# master_camera_io_2.net
KiCad netlist of a schematic drawn in EAGLE
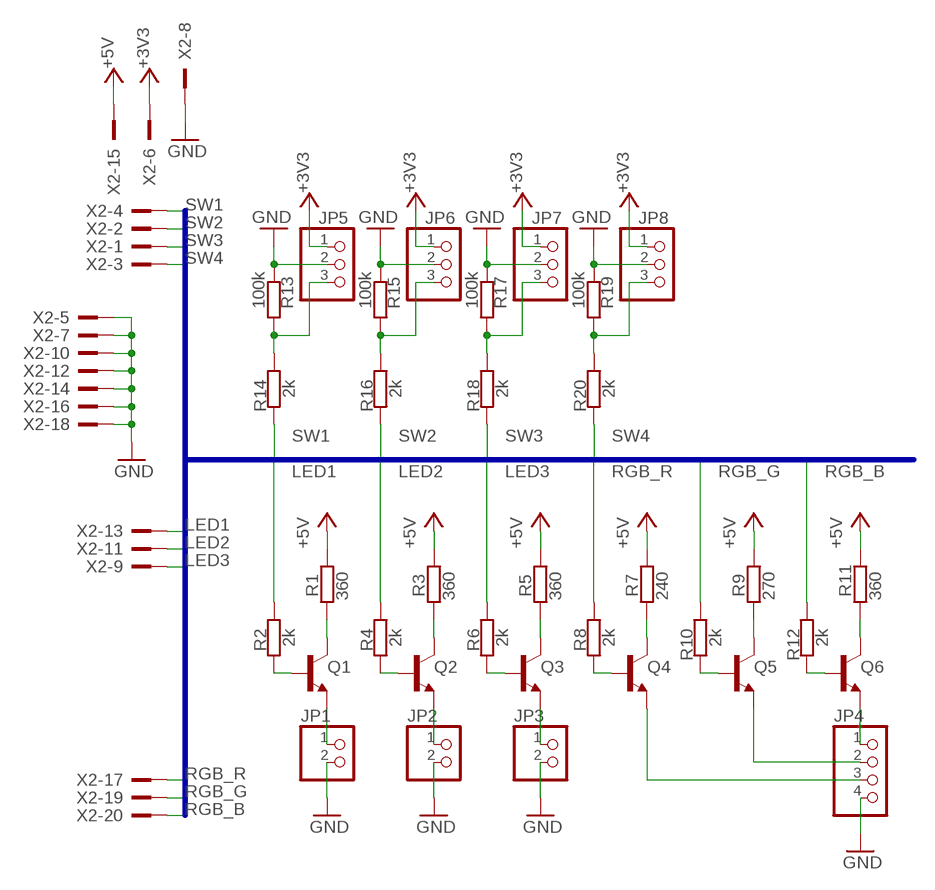
[diagram p0: schematic, sheet 1]

(export (version "E")
  (design (tool "Eeschema 10.0.6"))
  (components
    (comp (ref "JP1")
      (value "PINHD-1X2")
      (footprint "eagle-import:1X02")
      (libsource (lib "eagle-import") (part "PINHD-1X2"))
    )
    (comp (ref "JP2")
      (value "PINHD-1X2")
      (footprint "eagle-import:1X02")
      (libsource (lib "eagle-import") (part "PINHD-1X2"))
    )
    (comp (ref "JP3")
      (value "PINHD-1X2")
      (footprint "eagle-import:1X02")
      (libsource (lib "eagle-import") (part "PINHD-1X2"))
    )
    (comp (ref "JP4")
      (value "PINHD-1X4")
      (footprint "eagle-import:1X04")
      (libsource (lib "eagle-import") (part "PINHD-1X4"))
    )
    (comp (ref "JP5")
      (value "PINHD-1X3")
      (footprint "eagle-import:1X03")
      (libsource (lib "eagle-import") (part "PINHD-1X3"))
    )
    (comp (ref "JP6")
      (value "PINHD-1X3")
      (footprint "eagle-import:1X03")
      (libsource (lib "eagle-import") (part "PINHD-1X3"))
    )
    (comp (ref "JP7")
      (value "PINHD-1X3")
      (footprint "eagle-import:1X03")
      (libsource (lib "eagle-import") (part "PINHD-1X3"))
    )
    (comp (ref "JP8")
      (value "PINHD-1X3")
      (footprint "eagle-import:1X03")
      (libsource (lib "eagle-import") (part "PINHD-1X3"))
    )
    (comp (ref "Q1")
      (value "BC850SMD")
      (footprint "eagle-import:SOT23-BEC")
      (libsource (lib "eagle-import") (part "BC850SMD"))
    )
    (comp (ref "Q2")
      (value "BC850SMD")
      (footprint "eagle-import:SOT23-BEC")
      (libsource (lib "eagle-import") (part "BC850SMD"))
    )
    (comp (ref "Q3")
      (value "BC850SMD")
      (footprint "eagle-import:SOT23-BEC")
      (libsource (lib "eagle-import") (part "BC850SMD"))
    )
    (comp (ref "Q4")
      (value "BC850SMD")
      (footprint "eagle-import:SOT23-BEC")
      (libsource (lib "eagle-import") (part "BC850SMD"))
    )
    (comp (ref "Q5")
      (value "BC850SMD")
      (footprint "eagle-import:SOT23-BEC")
      (libsource (lib "eagle-import") (part "BC850SMD"))
    )
    (comp (ref "Q6")
      (value "BC850SMD")
      (footprint "eagle-import:SOT23-BEC")
      (libsource (lib "eagle-import") (part "BC850SMD"))
    )
    (comp (ref "R1")
      (value "360")
      (footprint "eagle-import:R0805")
      (libsource (lib "eagle-import") (part "R-EU_R0805"))
    )
    (comp (ref "R2")
      (value "2k")
      (footprint "eagle-import:R0805")
      (libsource (lib "eagle-import") (part "R-EU_R0805"))
    )
    (comp (ref "R3")
      (value "360")
      (footprint "eagle-import:R0805")
      (libsource (lib "eagle-import") (part "R-EU_R0805"))
    )
    (comp (ref "R4")
      (value "2k")
      (footprint "eagle-import:R0805")
      (libsource (lib "eagle-import") (part "R-EU_R0805"))
    )
    (comp (ref "R5")
      (value "360")
      (footprint "eagle-import:R0805")
      (libsource (lib "eagle-import") (part "R-EU_R0805"))
    )
    (comp (ref "R6")
      (value "2k")
      (footprint "eagle-import:R0805")
      (libsource (lib "eagle-import") (part "R-EU_R0805"))
    )
    (comp (ref "R7")
      (value "240")
      (footprint "eagle-import:R0805")
      (libsource (lib "eagle-import") (part "R-EU_R0805"))
    )
    (comp (ref "R8")
      (value "2k")
      (footprint "eagle-import:R0805")
      (libsource (lib "eagle-import") (part "R-EU_R0805"))
    )
    (comp (ref "R9")
      (value "270")
      (footprint "eagle-import:R0805")
      (libsource (lib "eagle-import") (part "R-EU_R0805"))
    )
    (comp (ref "R10")
      (value "2k")
      (footprint "eagle-import:R0805")
      (libsource (lib "eagle-import") (part "R-EU_R0805"))
    )
    (comp (ref "R11")
      (value "360")
      (footprint "eagle-import:R0805")
      (libsource (lib "eagle-import") (part "R-EU_R0805"))
    )
    (comp (ref "R12")
      (value "2k")
      (footprint "eagle-import:R0805")
      (libsource (lib "eagle-import") (part "R-EU_R0805"))
    )
    (comp (ref "R13")
      (value "100k")
      (footprint "eagle-import:R0805")
      (libsource (lib "eagle-import") (part "R-EU_R0805"))
    )
    (comp (ref "R14")
      (value "2k")
      (footprint "eagle-import:R0805")
      (libsource (lib "eagle-import") (part "R-EU_R0805"))
    )
    (comp (ref "R15")
      (value "100k")
      (footprint "eagle-import:R0805")
      (libsource (lib "eagle-import") (part "R-EU_R0805"))
    )
    (comp (ref "R16")
      (value "2k")
      (footprint "eagle-import:R0805")
      (libsource (lib "eagle-import") (part "R-EU_R0805"))
    )
    (comp (ref "R17")
      (value "100k")
      (footprint "eagle-import:R0805")
      (libsource (lib "eagle-import") (part "R-EU_R0805"))
    )
    (comp (ref "R18")
      (value "2k")
      (footprint "eagle-import:R0805")
      (libsource (lib "eagle-import") (part "R-EU_R0805"))
    )
    (comp (ref "R19")
      (value "100k")
      (footprint "eagle-import:R0805")
      (libsource (lib "eagle-import") (part "R-EU_R0805"))
    )
    (comp (ref "R20")
      (value "2k")
      (footprint "eagle-import:R0805")
      (libsource (lib "eagle-import") (part "R-EU_R0805"))
    )
    (comp (ref "X2")
      (value "2520-")
      (footprint "eagle-import:PAK100_2500-20")
      (libsource (lib "eagle-import") (part "2520-"))
    )
  )
  (nets
    (net (code "1") (name "+3V3") (class "Default")
      (node (ref "JP5") (pin "1") (pinfunction "1_1") (pintype "passive"))
      (node (ref "JP6") (pin "1") (pinfunction "1_1") (pintype "passive"))
      (node (ref "JP7") (pin "1") (pinfunction "1_1") (pintype "passive"))
      (node (ref "JP8") (pin "1") (pinfunction "1_1") (pintype "passive"))
      (node (ref "X2") (pin "6") (pinfunction "KL_6") (pintype "passive"))
    )
    (net (code "2") (name "+5V") (class "Default")
      (node (ref "R1") (pin "2") (pinfunction "2_2") (pintype "passive"))
      (node (ref "R11") (pin "2") (pinfunction "2_2") (pintype "passive"))
      (node (ref "R3") (pin "2") (pinfunction "2_2") (pintype "passive"))
      (node (ref "R5") (pin "2") (pinfunction "2_2") (pintype "passive"))
      (node (ref "R7") (pin "2") (pinfunction "2_2") (pintype "passive"))
      (node (ref "R9") (pin "2") (pinfunction "2_2") (pintype "passive"))
      (node (ref "X2") (pin "15") (pinfunction "KL_15") (pintype "passive"))
    )
    (net (code "3") (name "/LED1") (class "Default")
      (node (ref "R2") (pin "1") (pinfunction "1_1") (pintype "passive"))
      (node (ref "X2") (pin "13") (pinfunction "KL_13") (pintype "passive"))
    )
    (net (code "4") (name "/LED2") (class "Default")
      (node (ref "R4") (pin "1") (pinfunction "1_1") (pintype "passive"))
      (node (ref "X2") (pin "11") (pinfunction "KL_11") (pintype "passive"))
    )
    (net (code "5") (name "/LED3") (class "Default")
      (node (ref "R6") (pin "1") (pinfunction "1_1") (pintype "passive"))
      (node (ref "X2") (pin "9") (pinfunction "KL_9") (pintype "passive"))
    )
    (net (code "6") (name "/RGB_B") (class "Default")
      (node (ref "R12") (pin "1") (pinfunction "1_1") (pintype "passive"))
      (node (ref "X2") (pin "20") (pinfunction "KL_20") (pintype "passive"))
    )
    (net (code "7") (name "/RGB_G") (class "Default")
      (node (ref "R10") (pin "1") (pinfunction "1_1") (pintype "passive"))
      (node (ref "X2") (pin "19") (pinfunction "KL_19") (pintype "passive"))
    )
    (net (code "8") (name "/RGB_R") (class "Default")
      (node (ref "R8") (pin "1") (pinfunction "1_1") (pintype "passive"))
      (node (ref "X2") (pin "17") (pinfunction "KL_17") (pintype "passive"))
    )
    (net (code "9") (name "/SW1") (class "Default")
      (node (ref "R14") (pin "2") (pinfunction "2_2") (pintype "passive"))
      (node (ref "X2") (pin "4") (pinfunction "KL_4") (pintype "passive"))
    )
    (net (code "10") (name "/SW2") (class "Default")
      (node (ref "R16") (pin "2") (pinfunction "2_2") (pintype "passive"))
      (node (ref "X2") (pin "2") (pinfunction "KL_2") (pintype "passive"))
    )
    (net (code "11") (name "/SW3") (class "Default")
      (node (ref "R18") (pin "2") (pinfunction "2_2") (pintype "passive"))
      (node (ref "X2") (pin "1") (pinfunction "KL_1") (pintype "passive"))
    )
    (net (code "12") (name "/SW4") (class "Default")
      (node (ref "R20") (pin "2") (pinfunction "2_2") (pintype "passive"))
      (node (ref "X2") (pin "3") (pinfunction "KL_3") (pintype "passive"))
    )
    (net (code "13") (name "GND") (class "Default")
      (node (ref "JP1") (pin "2") (pinfunction "2_2") (pintype "passive"))
      (node (ref "JP2") (pin "2") (pinfunction "2_2") (pintype "passive"))
      (node (ref "JP3") (pin "2") (pinfunction "2_2") (pintype "passive"))
      (node (ref "JP4") (pin "4") (pinfunction "4_4") (pintype "passive"))
      (node (ref "JP5") (pin "2") (pinfunction "2_2") (pintype "passive"))
      (node (ref "JP6") (pin "2") (pinfunction "2_2") (pintype "passive"))
      (node (ref "JP7") (pin "2") (pinfunction "2_2") (pintype "passive"))
      (node (ref "JP8") (pin "2") (pinfunction "2_2") (pintype "passive"))
      (node (ref "R13") (pin "2") (pinfunction "2_2") (pintype "passive"))
      (node (ref "R15") (pin "2") (pinfunction "2_2") (pintype "passive"))
      (node (ref "R17") (pin "2") (pinfunction "2_2") (pintype "passive"))
      (node (ref "R19") (pin "2") (pinfunction "2_2") (pintype "passive"))
      (node (ref "X2") (pin "10") (pinfunction "KL_10") (pintype "passive"))
      (node (ref "X2") (pin "12") (pinfunction "KL_12") (pintype "passive"))
      (node (ref "X2") (pin "14") (pinfunction "KL_14") (pintype "passive"))
      (node (ref "X2") (pin "16") (pinfunction "KL_16") (pintype "passive"))
      (node (ref "X2") (pin "18") (pinfunction "KL_18") (pintype "passive"))
      (node (ref "X2") (pin "5") (pinfunction "KL_5") (pintype "passive"))
      (node (ref "X2") (pin "7") (pinfunction "KL_7") (pintype "passive"))
      (node (ref "X2") (pin "8") (pinfunction "KL_8") (pintype "passive"))
    )
    (net (code "14") (name "Net-(JP1-Pad1)") (class "Default")
      (node (ref "JP1") (pin "1") (pinfunction "1_1") (pintype "passive"))
      (node (ref "Q1") (pin "E") (pinfunction "E_E") (pintype "passive"))
    )
    (net (code "15") (name "Net-(JP2-Pad1)") (class "Default")
      (node (ref "JP2") (pin "1") (pinfunction "1_1") (pintype "passive"))
      (node (ref "Q2") (pin "E") (pinfunction "E_E") (pintype "passive"))
    )
    (net (code "16") (name "Net-(JP3-Pad1)") (class "Default")
      (node (ref "JP3") (pin "1") (pinfunction "1_1") (pintype "passive"))
      (node (ref "Q3") (pin "E") (pinfunction "E_E") (pintype "passive"))
    )
    (net (code "17") (name "Net-(JP4-Pad1)") (class "Default")
      (node (ref "JP4") (pin "1") (pinfunction "1_1") (pintype "passive"))
      (node (ref "Q6") (pin "E") (pinfunction "E_E") (pintype "passive"))
    )
    (net (code "18") (name "Net-(JP4-Pad2)") (class "Default")
      (node (ref "JP4") (pin "2") (pinfunction "2_2") (pintype "passive"))
      (node (ref "Q5") (pin "E") (pinfunction "E_E") (pintype "passive"))
    )
    (net (code "19") (name "Net-(JP4-Pad3)") (class "Default")
      (node (ref "JP4") (pin "3") (pinfunction "3_3") (pintype "passive"))
      (node (ref "Q4") (pin "E") (pinfunction "E_E") (pintype "passive"))
    )
    (net (code "20") (name "Net-(JP5-Pad3)") (class "Default")
      (node (ref "JP5") (pin "3") (pinfunction "3_3") (pintype "passive"))
      (node (ref "R13") (pin "1") (pinfunction "1_1") (pintype "passive"))
      (node (ref "R14") (pin "1") (pinfunction "1_1") (pintype "passive"))
    )
    (net (code "21") (name "Net-(JP6-Pad3)") (class "Default")
      (node (ref "JP6") (pin "3") (pinfunction "3_3") (pintype "passive"))
      (node (ref "R15") (pin "1") (pinfunction "1_1") (pintype "passive"))
      (node (ref "R16") (pin "1") (pinfunction "1_1") (pintype "passive"))
    )
    (net (code "22") (name "Net-(JP7-Pad3)") (class "Default")
      (node (ref "JP7") (pin "3") (pinfunction "3_3") (pintype "passive"))
      (node (ref "R17") (pin "1") (pinfunction "1_1") (pintype "passive"))
      (node (ref "R18") (pin "1") (pinfunction "1_1") (pintype "passive"))
    )
    (net (code "23") (name "Net-(JP8-Pad3)") (class "Default")
      (node (ref "JP8") (pin "3") (pinfunction "3_3") (pintype "passive"))
      (node (ref "R19") (pin "1") (pinfunction "1_1") (pintype "passive"))
      (node (ref "R20") (pin "1") (pinfunction "1_1") (pintype "passive"))
    )
    (net (code "24") (name "Net-(Q1-PadB)") (class "Default")
      (node (ref "Q1") (pin "B") (pinfunction "B_B") (pintype "passive"))
      (node (ref "R2") (pin "2") (pinfunction "2_2") (pintype "passive"))
    )
    (net (code "25") (name "Net-(Q1-PadC)") (class "Default")
      (node (ref "Q1") (pin "C") (pinfunction "C_C") (pintype "passive"))
      (node (ref "R1") (pin "1") (pinfunction "1_1") (pintype "passive"))
    )
    (net (code "26") (name "Net-(Q2-PadB)") (class "Default")
      (node (ref "Q2") (pin "B") (pinfunction "B_B") (pintype "passive"))
      (node (ref "R4") (pin "2") (pinfunction "2_2") (pintype "passive"))
    )
    (net (code "27") (name "Net-(Q2-PadC)") (class "Default")
      (node (ref "Q2") (pin "C") (pinfunction "C_C") (pintype "passive"))
      (node (ref "R3") (pin "1") (pinfunction "1_1") (pintype "passive"))
    )
    (net (code "28") (name "Net-(Q3-PadB)") (class "Default")
      (node (ref "Q3") (pin "B") (pinfunction "B_B") (pintype "passive"))
      (node (ref "R6") (pin "2") (pinfunction "2_2") (pintype "passive"))
    )
    (net (code "29") (name "Net-(Q3-PadC)") (class "Default")
      (node (ref "Q3") (pin "C") (pinfunction "C_C") (pintype "passive"))
      (node (ref "R5") (pin "1") (pinfunction "1_1") (pintype "passive"))
    )
    (net (code "30") (name "Net-(Q4-PadB)") (class "Default")
      (node (ref "Q4") (pin "B") (pinfunction "B_B") (pintype "passive"))
      (node (ref "R8") (pin "2") (pinfunction "2_2") (pintype "passive"))
    )
    (net (code "31") (name "Net-(Q4-PadC)") (class "Default")
      (node (ref "Q4") (pin "C") (pinfunction "C_C") (pintype "passive"))
      (node (ref "R7") (pin "1") (pinfunction "1_1") (pintype "passive"))
    )
    (net (code "32") (name "Net-(Q5-PadB)") (class "Default")
      (node (ref "Q5") (pin "B") (pinfunction "B_B") (pintype "passive"))
      (node (ref "R10") (pin "2") (pinfunction "2_2") (pintype "passive"))
    )
    (net (code "33") (name "Net-(Q5-PadC)") (class "Default")
      (node (ref "Q5") (pin "C") (pinfunction "C_C") (pintype "passive"))
      (node (ref "R9") (pin "1") (pinfunction "1_1") (pintype "passive"))
    )
    (net (code "34") (name "Net-(Q6-PadB)") (class "Default")
      (node (ref "Q6") (pin "B") (pinfunction "B_B") (pintype "passive"))
      (node (ref "R12") (pin "2") (pinfunction "2_2") (pintype "passive"))
    )
    (net (code "35") (name "Net-(Q6-PadC)") (class "Default")
      (node (ref "Q6") (pin "C") (pinfunction "C_C") (pintype "passive"))
      (node (ref "R11") (pin "1") (pinfunction "1_1") (pintype "passive"))
    )
  )
)
